# Proto_shield_REV3-chris.net
KiCad netlist of a schematic drawn in EAGLE
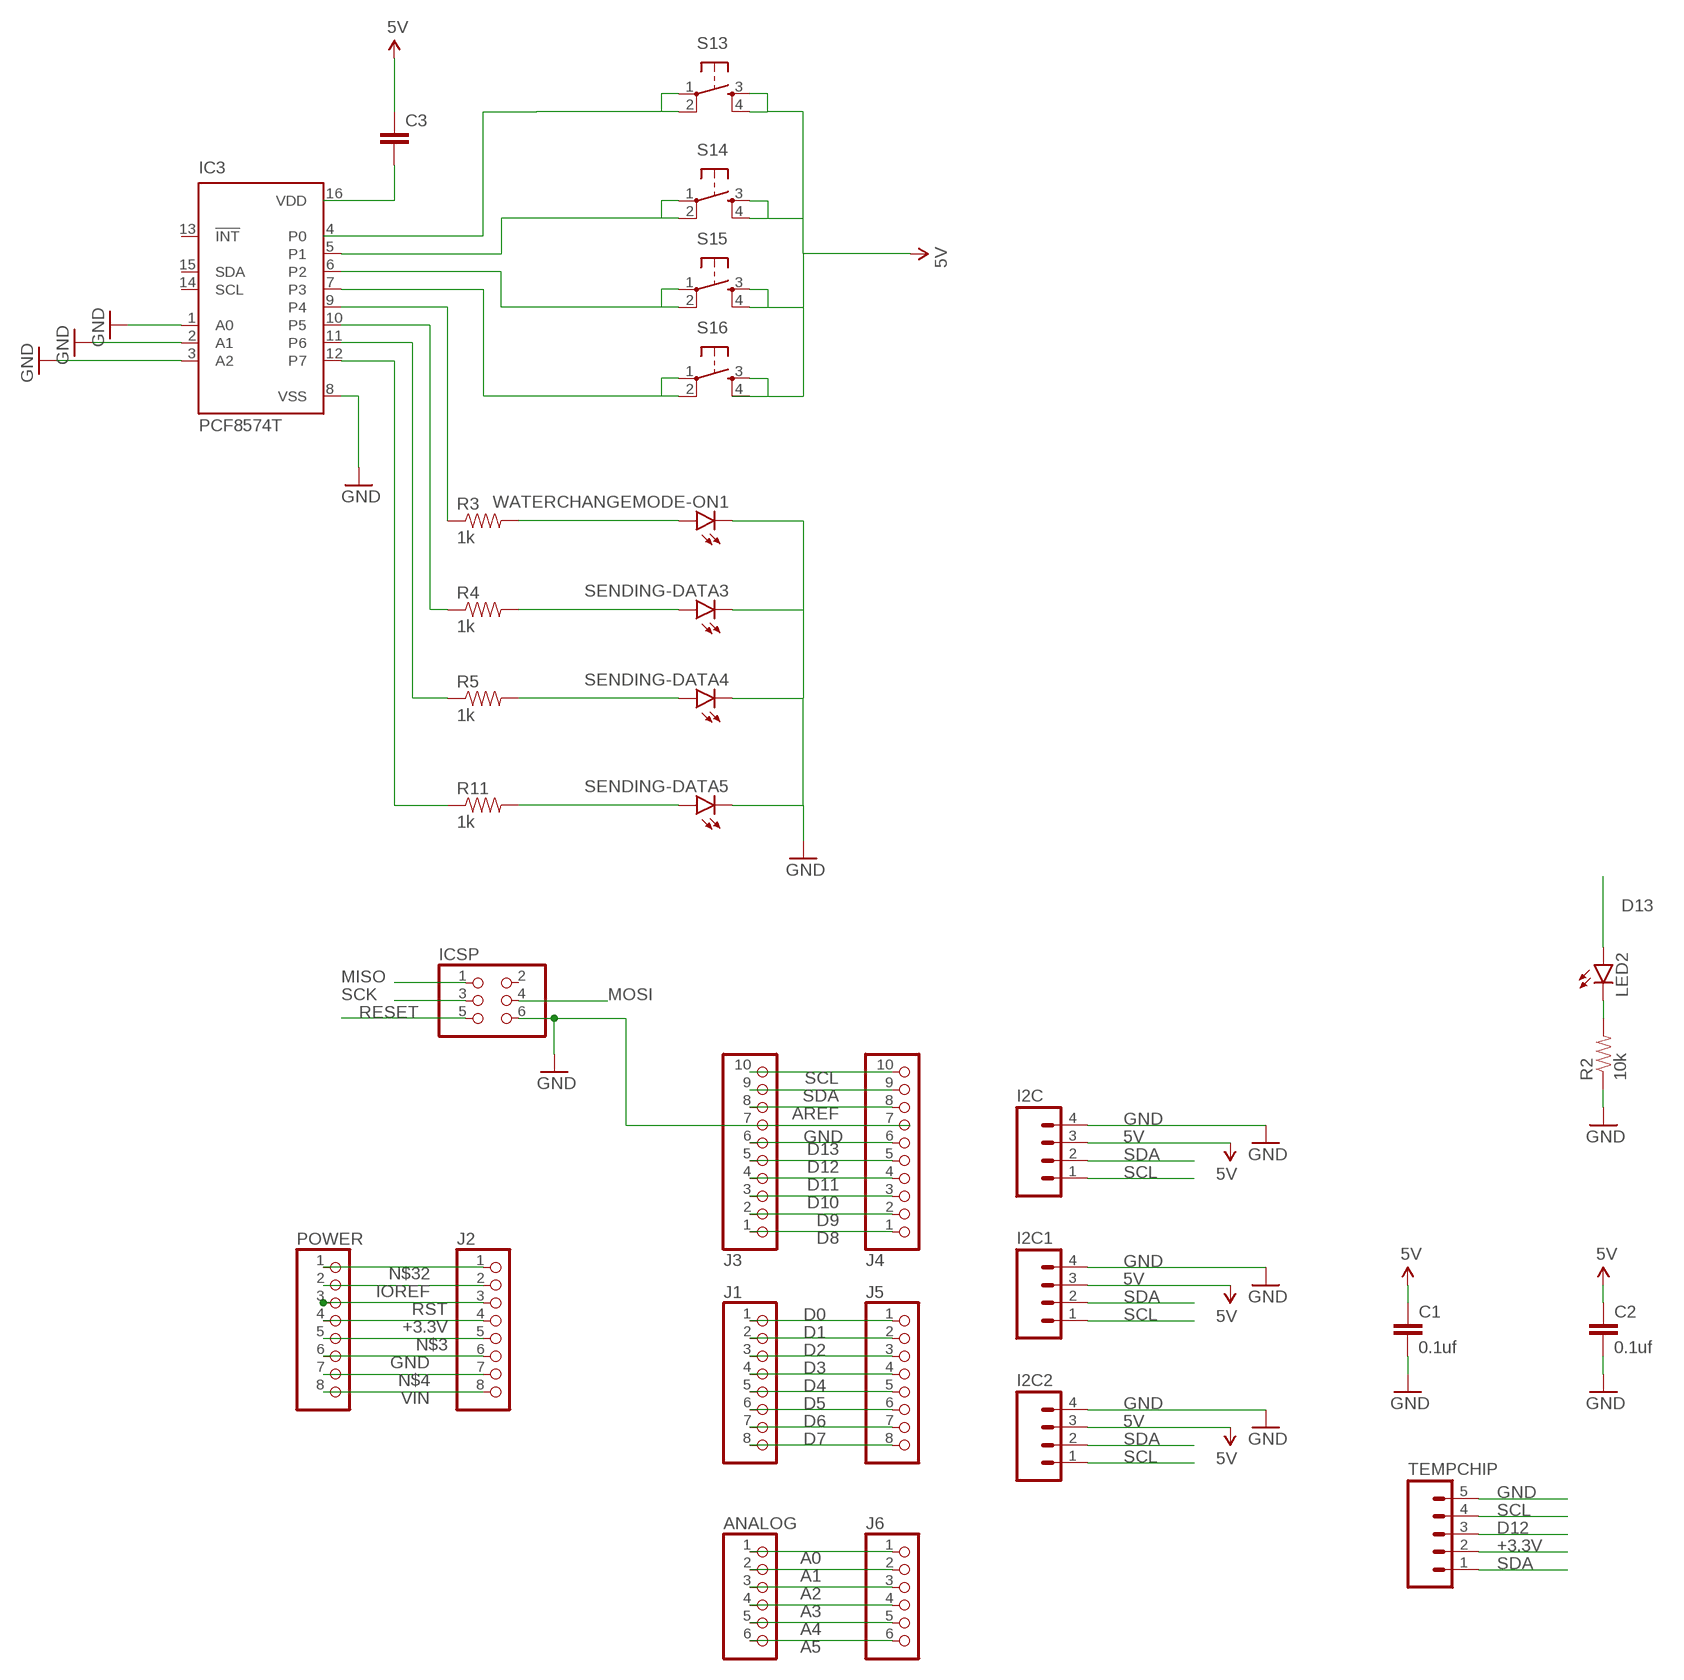
[diagram p0: schematic, sheet 1]

(export (version "E")
  (design (tool "Eeschema 10.0.6"))
  (components
    (comp (ref "ANALOG")
      (value "PINHD-1X6")
      (footprint "eagle-import:1X06")
      (libsource (lib "eagle-import") (part "PINHD-1X6"))
    )
    (comp (ref "C1")
      (value "0.1uf")
      (footprint "eagle-import:CAP-PTH-SMALL2")
      (libsource (lib "eagle-import") (part "CAPPTH2"))
    )
    (comp (ref "C2")
      (value "0.1uf")
      (footprint "eagle-import:CAP-PTH-SMALL2")
      (libsource (lib "eagle-import") (part "CAPPTH2"))
    )
    (comp (ref "C3")
      (value "CAPPTH2")
      (footprint "eagle-import:CAP-PTH-SMALL2")
      (libsource (lib "eagle-import") (part "CAPPTH2"))
    )
    (comp (ref "I2C")
      (value "M04PTH")
      (footprint "eagle-import:1X04")
      (libsource (lib "eagle-import") (part "M04PTH"))
    )
    (comp (ref "I2C1")
      (value "M04PTH")
      (footprint "eagle-import:1X04")
      (libsource (lib "eagle-import") (part "M04PTH"))
    )
    (comp (ref "I2C2")
      (value "M04PTH")
      (footprint "eagle-import:1X04")
      (libsource (lib "eagle-import") (part "M04PTH"))
    )
    (comp (ref "IC3")
      (value "PCF8574T")
      (footprint "eagle-import:SO16W")
      (libsource (lib "eagle-import") (part "PCF8574T"))
    )
    (comp (ref "ICSP")
      (value "PINHD-2X3")
      (footprint "eagle-import:2X03")
      (libsource (lib "eagle-import") (part "PINHD-2X3"))
    )
    (comp (ref "J1")
      (value "PINHD-1X8TH")
      (footprint "eagle-import:1X08-TH")
      (libsource (lib "eagle-import") (part "PINHD-1X8TH"))
    )
    (comp (ref "J2")
      (value "PINHD-1X8TH")
      (footprint "eagle-import:1X08-TH")
      (libsource (lib "eagle-import") (part "PINHD-1X8TH"))
    )
    (comp (ref "J3")
      (value "PINHD-1X10TH")
      (footprint "eagle-import:1X10-TH")
      (libsource (lib "eagle-import") (part "PINHD-1X10TH"))
    )
    (comp (ref "J4")
      (value "PINHD-1X10TH")
      (footprint "eagle-import:1X10-TH")
      (libsource (lib "eagle-import") (part "PINHD-1X10TH"))
    )
    (comp (ref "J5")
      (value "PINHD-1X8TH")
      (footprint "eagle-import:1X08-TH")
      (libsource (lib "eagle-import") (part "PINHD-1X8TH"))
    )
    (comp (ref "J6")
      (value "PINHD-1X6")
      (footprint "eagle-import:1X06")
      (libsource (lib "eagle-import") (part "PINHD-1X6"))
    )
    (comp (ref "LED2")
      (value "LED5MM")
      (footprint "eagle-import:LED5MM")
      (libsource (lib "eagle-import") (part "LED5MM"))
    )
    (comp (ref "POWER")
      (value "PINHD-1X8TH")
      (footprint "eagle-import:1X08-TH")
      (libsource (lib "eagle-import") (part "PINHD-1X8TH"))
    )
    (comp (ref "R2")
      (value "10k")
      (footprint "eagle-import:AXIAL-0.3")
      (libsource (lib "eagle-import") (part "RESISTORAXIAL-0.3"))
    )
    (comp (ref "R3")
      (value "1k")
      (footprint "eagle-import:AXIAL-0.3")
      (libsource (lib "eagle-import") (part "RESISTORAXIAL-0.3"))
    )
    (comp (ref "R4")
      (value "1k")
      (footprint "eagle-import:AXIAL-0.3")
      (libsource (lib "eagle-import") (part "RESISTORAXIAL-0.3"))
    )
    (comp (ref "R5")
      (value "1k")
      (footprint "eagle-import:AXIAL-0.3")
      (libsource (lib "eagle-import") (part "RESISTORAXIAL-0.3"))
    )
    (comp (ref "R11")
      (value "1k")
      (footprint "eagle-import:AXIAL-0.3")
      (libsource (lib "eagle-import") (part "RESISTORAXIAL-0.3"))
    )
    (comp (ref "S13")
      (value "TAC_SWITCHPTH")
      (footprint "eagle-import:TACTILE-PTH")
      (libsource (lib "eagle-import") (part "TAC_SWITCHPTH"))
    )
    (comp (ref "S14")
      (value "TAC_SWITCHPTH")
      (footprint "eagle-import:TACTILE-PTH")
      (libsource (lib "eagle-import") (part "TAC_SWITCHPTH"))
    )
    (comp (ref "S15")
      (value "TAC_SWITCHPTH")
      (footprint "eagle-import:TACTILE-PTH")
      (libsource (lib "eagle-import") (part "TAC_SWITCHPTH"))
    )
    (comp (ref "S16")
      (value "TAC_SWITCHPTH")
      (footprint "eagle-import:TACTILE-PTH")
      (libsource (lib "eagle-import") (part "TAC_SWITCHPTH"))
    )
    (comp (ref "SENDING-DATA3")
      (value "LED3MM")
      (footprint "eagle-import:LED3MM")
      (libsource (lib "eagle-import") (part "LED3MM"))
    )
    (comp (ref "SENDING-DATA4")
      (value "LED3MM")
      (footprint "eagle-import:LED3MM")
      (libsource (lib "eagle-import") (part "LED3MM"))
    )
    (comp (ref "SENDING-DATA5")
      (value "LED3MM")
      (footprint "eagle-import:LED3MM")
      (libsource (lib "eagle-import") (part "LED3MM"))
    )
    (comp (ref "TEMPCHIP")
      (value "M051.27MM")
      (footprint "eagle-import:1X05-1.27MM")
      (libsource (lib "eagle-import") (part "M051.27MM"))
    )
    (comp (ref "WATERCHANGEMODE-ON1")
      (value "LED3MM")
      (footprint "eagle-import:LED3MM")
      (libsource (lib "eagle-import") (part "LED3MM"))
    )
  )
  (nets
    (net (code "1") (name "/+3.3V") (class "Default")
      (node (ref "J2") (pin "4") (pinfunction "4_4") (pintype "passive"))
      (node (ref "POWER") (pin "4") (pinfunction "4_4") (pintype "passive"))
      (node (ref "TEMPCHIP") (pin "2") (pinfunction "2_2") (pintype "passive"))
    )
    (net (code "2") (name "/A0") (class "Default")
      (node (ref "ANALOG") (pin "1") (pinfunction "1_1") (pintype "passive"))
      (node (ref "J6") (pin "1") (pinfunction "1_1") (pintype "passive"))
    )
    (net (code "3") (name "/A1") (class "Default")
      (node (ref "ANALOG") (pin "2") (pinfunction "2_2") (pintype "passive"))
      (node (ref "J6") (pin "2") (pinfunction "2_2") (pintype "passive"))
    )
    (net (code "4") (name "/A2") (class "Default")
      (node (ref "ANALOG") (pin "3") (pinfunction "3_3") (pintype "passive"))
      (node (ref "J6") (pin "3") (pinfunction "3_3") (pintype "passive"))
    )
    (net (code "5") (name "/A3") (class "Default")
      (node (ref "ANALOG") (pin "4") (pinfunction "4_4") (pintype "passive"))
      (node (ref "J6") (pin "4") (pinfunction "4_4") (pintype "passive"))
    )
    (net (code "6") (name "/A4") (class "Default")
      (node (ref "ANALOG") (pin "5") (pinfunction "5_5") (pintype "passive"))
      (node (ref "J6") (pin "5") (pinfunction "5_5") (pintype "passive"))
    )
    (net (code "7") (name "/A5") (class "Default")
      (node (ref "ANALOG") (pin "6") (pinfunction "6_6") (pintype "passive"))
      (node (ref "J6") (pin "6") (pinfunction "6_6") (pintype "passive"))
    )
    (net (code "8") (name "/AREF") (class "Default")
      (node (ref "J3") (pin "8") (pinfunction "8_8") (pintype "passive"))
      (node (ref "J4") (pin "8") (pinfunction "8_8") (pintype "passive"))
    )
    (net (code "9") (name "/D0") (class "Default")
      (node (ref "J1") (pin "1") (pinfunction "1_1") (pintype "passive"))
      (node (ref "J5") (pin "1") (pinfunction "1_1") (pintype "passive"))
    )
    (net (code "10") (name "/D1") (class "Default")
      (node (ref "J1") (pin "2") (pinfunction "2_2") (pintype "passive"))
      (node (ref "J5") (pin "2") (pinfunction "2_2") (pintype "passive"))
    )
    (net (code "11") (name "/D2") (class "Default")
      (node (ref "J1") (pin "3") (pinfunction "3_3") (pintype "passive"))
      (node (ref "J5") (pin "3") (pinfunction "3_3") (pintype "passive"))
    )
    (net (code "12") (name "/D3") (class "Default")
      (node (ref "J1") (pin "4") (pinfunction "4_4") (pintype "passive"))
      (node (ref "J5") (pin "4") (pinfunction "4_4") (pintype "passive"))
    )
    (net (code "13") (name "/D4") (class "Default")
      (node (ref "J1") (pin "5") (pinfunction "5_5") (pintype "passive"))
      (node (ref "J5") (pin "5") (pinfunction "5_5") (pintype "passive"))
    )
    (net (code "14") (name "/D5") (class "Default")
      (node (ref "J1") (pin "6") (pinfunction "6_6") (pintype "passive"))
      (node (ref "J5") (pin "6") (pinfunction "6_6") (pintype "passive"))
    )
    (net (code "15") (name "/D6") (class "Default")
      (node (ref "J1") (pin "7") (pinfunction "7_7") (pintype "passive"))
      (node (ref "J5") (pin "7") (pinfunction "7_7") (pintype "passive"))
    )
    (net (code "16") (name "/D7") (class "Default")
      (node (ref "J1") (pin "8") (pinfunction "8_8") (pintype "passive"))
      (node (ref "J5") (pin "8") (pinfunction "8_8") (pintype "passive"))
    )
    (net (code "17") (name "/D8") (class "Default")
      (node (ref "J3") (pin "1") (pinfunction "1_1") (pintype "passive"))
      (node (ref "J4") (pin "1") (pinfunction "1_1") (pintype "passive"))
    )
    (net (code "18") (name "/D9") (class "Default")
      (node (ref "J3") (pin "2") (pinfunction "2_2") (pintype "passive"))
      (node (ref "J4") (pin "2") (pinfunction "2_2") (pintype "passive"))
    )
    (net (code "19") (name "/D10") (class "Default")
      (node (ref "J3") (pin "3") (pinfunction "3_3") (pintype "passive"))
      (node (ref "J4") (pin "3") (pinfunction "3_3") (pintype "passive"))
    )
    (net (code "20") (name "/D11") (class "Default")
      (node (ref "J3") (pin "4") (pinfunction "4_4") (pintype "passive"))
      (node (ref "J4") (pin "4") (pinfunction "4_4") (pintype "passive"))
    )
    (net (code "21") (name "/D12") (class "Default")
      (node (ref "J3") (pin "5") (pinfunction "5_5") (pintype "passive"))
      (node (ref "J4") (pin "5") (pinfunction "5_5") (pintype "passive"))
      (node (ref "TEMPCHIP") (pin "3") (pinfunction "3_3") (pintype "passive"))
    )
    (net (code "22") (name "/D13") (class "Default")
      (node (ref "J3") (pin "6") (pinfunction "6_6") (pintype "passive"))
      (node (ref "J4") (pin "6") (pinfunction "6_6") (pintype "passive"))
      (node (ref "LED2") (pin "A") (pinfunction "A_A") (pintype "passive"))
    )
    (net (code "23") (name "/IOREF") (class "Default")
      (node (ref "J2") (pin "2") (pinfunction "2_2") (pintype "passive"))
      (node (ref "POWER") (pin "2") (pinfunction "2_2") (pintype "passive"))
    )
    (net (code "24") (name "/MISO") (class "Default")
      (node (ref "ICSP") (pin "1") (pinfunction "1_1") (pintype "passive"))
    )
    (net (code "25") (name "/MOSI") (class "Default")
      (node (ref "ICSP") (pin "4") (pinfunction "4_4") (pintype "passive"))
    )
    (net (code "26") (name "/N$3") (class "Default")
      (node (ref "J2") (pin "5") (pinfunction "5_5") (pintype "passive"))
      (node (ref "POWER") (pin "5") (pinfunction "5_5") (pintype "passive"))
    )
    (net (code "27") (name "/N$4") (class "Default")
      (node (ref "J2") (pin "7") (pinfunction "7_7") (pintype "passive"))
      (node (ref "POWER") (pin "7") (pinfunction "7_7") (pintype "passive"))
    )
    (net (code "28") (name "/N$32") (class "Default")
      (node (ref "J2") (pin "1") (pinfunction "1_1") (pintype "passive"))
      (node (ref "POWER") (pin "1") (pinfunction "1_1") (pintype "passive"))
    )
    (net (code "29") (name "/RESET") (class "Default")
      (node (ref "ICSP") (pin "5") (pinfunction "5_5") (pintype "passive"))
    )
    (net (code "30") (name "/RST") (class "Default")
      (node (ref "J2") (pin "3") (pinfunction "3_3") (pintype "passive"))
      (node (ref "POWER") (pin "3") (pinfunction "3_3") (pintype "passive"))
    )
    (net (code "31") (name "/SCK") (class "Default")
      (node (ref "ICSP") (pin "3") (pinfunction "3_3") (pintype "passive"))
    )
    (net (code "32") (name "/SCL") (class "Default")
      (node (ref "I2C") (pin "1") (pinfunction "1_1") (pintype "passive"))
      (node (ref "I2C1") (pin "1") (pinfunction "1_1") (pintype "passive"))
      (node (ref "I2C2") (pin "1") (pinfunction "1_1") (pintype "passive"))
      (node (ref "J3") (pin "10") (pinfunction "10_10") (pintype "passive"))
      (node (ref "J4") (pin "10") (pinfunction "10_10") (pintype "passive"))
      (node (ref "TEMPCHIP") (pin "4") (pinfunction "4_4") (pintype "passive"))
    )
    (net (code "33") (name "/SDA") (class "Default")
      (node (ref "I2C") (pin "2") (pinfunction "2_2") (pintype "passive"))
      (node (ref "I2C1") (pin "2") (pinfunction "2_2") (pintype "passive"))
      (node (ref "I2C2") (pin "2") (pinfunction "2_2") (pintype "passive"))
      (node (ref "J3") (pin "9") (pinfunction "9_9") (pintype "passive"))
      (node (ref "J4") (pin "9") (pinfunction "9_9") (pintype "passive"))
      (node (ref "TEMPCHIP") (pin "1") (pinfunction "1_1") (pintype "passive"))
    )
    (net (code "34") (name "/VDD") (class "Default")
      (node (ref "IC3") (pin "16") (pinfunction "VDD_16") (pintype "power_in"))
    )
    (net (code "35") (name "/VIN") (class "Default")
      (node (ref "J2") (pin "8") (pinfunction "8_8") (pintype "passive"))
      (node (ref "POWER") (pin "8") (pinfunction "8_8") (pintype "passive"))
    )
    (net (code "36") (name "5V") (class "Default")
      (node (ref "C1") (pin "1") (pinfunction "1_1") (pintype "passive"))
      (node (ref "C2") (pin "1") (pinfunction "1_1") (pintype "passive"))
      (node (ref "C3") (pin "1") (pinfunction "1_1") (pintype "passive"))
      (node (ref "I2C") (pin "3") (pinfunction "3_3") (pintype "passive"))
      (node (ref "I2C1") (pin "3") (pinfunction "3_3") (pintype "passive"))
      (node (ref "I2C2") (pin "3") (pinfunction "3_3") (pintype "passive"))
      (node (ref "S13") (pin "3") (pinfunction "3_3") (pintype "passive"))
      (node (ref "S13") (pin "4") (pinfunction "4_4") (pintype "passive"))
      (node (ref "S14") (pin "3") (pinfunction "3_3") (pintype "passive"))
      (node (ref "S14") (pin "4") (pinfunction "4_4") (pintype "passive"))
      (node (ref "S15") (pin "3") (pinfunction "3_3") (pintype "passive"))
      (node (ref "S15") (pin "4") (pinfunction "4_4") (pintype "passive"))
      (node (ref "S16") (pin "3") (pinfunction "3_3") (pintype "passive"))
      (node (ref "S16") (pin "4") (pinfunction "4_4") (pintype "passive"))
    )
    (net (code "37") (name "GND") (class "Default")
      (node (ref "C1") (pin "2") (pinfunction "2_2") (pintype "passive"))
      (node (ref "C2") (pin "2") (pinfunction "2_2") (pintype "passive"))
      (node (ref "I2C") (pin "4") (pinfunction "4_4") (pintype "passive"))
      (node (ref "I2C1") (pin "4") (pinfunction "4_4") (pintype "passive"))
      (node (ref "I2C2") (pin "4") (pinfunction "4_4") (pintype "passive"))
      (node (ref "IC3") (pin "1") (pinfunction "A0_1") (pintype "input"))
      (node (ref "IC3") (pin "2") (pinfunction "A1_2") (pintype "input"))
      (node (ref "IC3") (pin "3") (pinfunction "A2_3") (pintype "input"))
      (node (ref "IC3") (pin "8") (pinfunction "VSS_8") (pintype "power_in"))
      (node (ref "ICSP") (pin "6") (pinfunction "6_6") (pintype "passive"))
      (node (ref "J2") (pin "6") (pinfunction "6_6") (pintype "passive"))
      (node (ref "POWER") (pin "6") (pinfunction "6_6") (pintype "passive"))
      (node (ref "R2") (pin "P$1") (pinfunction "1_P$1") (pintype "passive"))
      (node (ref "SENDING-DATA3") (pin "K") (pinfunction "C_K") (pintype "passive"))
      (node (ref "SENDING-DATA4") (pin "K") (pinfunction "C_K") (pintype "passive"))
      (node (ref "SENDING-DATA5") (pin "K") (pinfunction "C_K") (pintype "passive"))
      (node (ref "TEMPCHIP") (pin "5") (pinfunction "5_5") (pintype "passive"))
      (node (ref "WATERCHANGEMODE-ON1") (pin "K") (pinfunction "C_K") (pintype "passive"))
    )
    (net (code "38") (name "Net-(IC3-P1)") (class "Default")
      (node (ref "IC3") (pin "5") (pinfunction "P1_5") (pintype "bidirectional"))
      (node (ref "S14") (pin "1") (pinfunction "1_1") (pintype "passive"))
      (node (ref "S14") (pin "2") (pinfunction "2_2") (pintype "passive"))
    )
    (net (code "39") (name "Net-(IC3-P2)") (class "Default")
      (node (ref "IC3") (pin "6") (pinfunction "P2_6") (pintype "bidirectional"))
      (node (ref "S15") (pin "1") (pinfunction "1_1") (pintype "passive"))
      (node (ref "S15") (pin "2") (pinfunction "2_2") (pintype "passive"))
    )
    (net (code "40") (name "Net-(IC3-P3)") (class "Default")
      (node (ref "IC3") (pin "7") (pinfunction "P3_7") (pintype "bidirectional"))
      (node (ref "S16") (pin "1") (pinfunction "1_1") (pintype "passive"))
      (node (ref "S16") (pin "2") (pinfunction "2_2") (pintype "passive"))
    )
    (net (code "41") (name "Net-(IC3-P4)") (class "Default")
      (node (ref "IC3") (pin "9") (pinfunction "P4_9") (pintype "bidirectional"))
      (node (ref "R3") (pin "P$1") (pinfunction "1_P$1") (pintype "passive"))
    )
    (net (code "42") (name "Net-(IC3-P5)") (class "Default")
      (node (ref "IC3") (pin "10") (pinfunction "P5_10") (pintype "bidirectional"))
      (node (ref "R4") (pin "P$1") (pinfunction "1_P$1") (pintype "passive"))
    )
    (net (code "43") (name "Net-(IC3-P6)") (class "Default")
      (node (ref "IC3") (pin "11") (pinfunction "P6_11") (pintype "bidirectional"))
      (node (ref "R5") (pin "P$1") (pinfunction "1_P$1") (pintype "passive"))
    )
    (net (code "44") (name "Net-(IC3-P7)") (class "Default")
      (node (ref "IC3") (pin "12") (pinfunction "P7_12") (pintype "bidirectional"))
      (node (ref "R11") (pin "P$1") (pinfunction "1_P$1") (pintype "passive"))
    )
    (net (code "45") (name "Net-(LED2-C)") (class "Default")
      (node (ref "LED2") (pin "K") (pinfunction "C_K") (pintype "passive"))
      (node (ref "R2") (pin "P$2") (pinfunction "2_P$2") (pintype "passive"))
    )
    (net (code "46") (name "Net-(R3-2)") (class "Default")
      (node (ref "R3") (pin "P$2") (pinfunction "2_P$2") (pintype "passive"))
      (node (ref "WATERCHANGEMODE-ON1") (pin "A") (pinfunction "A_A") (pintype "passive"))
    )
    (net (code "47") (name "Net-(R4-2)") (class "Default")
      (node (ref "R4") (pin "P$2") (pinfunction "2_P$2") (pintype "passive"))
      (node (ref "SENDING-DATA3") (pin "A") (pinfunction "A_A") (pintype "passive"))
    )
    (net (code "48") (name "Net-(R5-2)") (class "Default")
      (node (ref "R5") (pin "P$2") (pinfunction "2_P$2") (pintype "passive"))
      (node (ref "SENDING-DATA4") (pin "A") (pinfunction "A_A") (pintype "passive"))
    )
    (net (code "49") (name "Net-(R11-2)") (class "Default")
      (node (ref "R11") (pin "P$2") (pinfunction "2_P$2") (pintype "passive"))
      (node (ref "SENDING-DATA5") (pin "A") (pinfunction "A_A") (pintype "passive"))
    )
    (net (code "50") (name "Net-(S13-Pad1)") (class "Default")
      (node (ref "S13") (pin "1") (pinfunction "1_1") (pintype "passive"))
      (node (ref "S13") (pin "2") (pinfunction "2_2") (pintype "passive"))
    )
    (net (code "51") (name "unconnected-(C3-Pad2)") (class "Default")
      (node (ref "C3") (pin "2") (pinfunction "2_2") (pintype "passive"))
    )
    (net (code "52") (name "unconnected-(IC3-P0-Pad4)") (class "Default")
      (node (ref "IC3") (pin "4") (pinfunction "P0_4") (pintype "bidirectional"))
    )
    (net (code "53") (name "unconnected-(IC3-SCL-Pad14)") (class "Default")
      (node (ref "IC3") (pin "14") (pinfunction "SCL_14") (pintype "input"))
    )
    (net (code "54") (name "unconnected-(IC3-SDA-Pad15)") (class "Default")
      (node (ref "IC3") (pin "15") (pinfunction "SDA_15") (pintype "bidirectional"))
    )
    (net (code "55") (name "unconnected-(IC3-~{INT}-Pad13)") (class "Default")
      (node (ref "IC3") (pin "13") (pinfunction "~{INT}_13") (pintype "output"))
    )
    (net (code "56") (name "unconnected-(ICSP-Pad2)") (class "Default")
      (node (ref "ICSP") (pin "2") (pinfunction "2_2") (pintype "passive"))
    )
    (net (code "57") (name "unconnected-(J3-Pad7)") (class "Default")
      (node (ref "J3") (pin "7") (pinfunction "7_7") (pintype "passive"))
    )
    (net (code "58") (name "unconnected-(J4-Pad7)") (class "Default")
      (node (ref "J4") (pin "7") (pinfunction "7_7") (pintype "passive"))
    )
  )
)
